# Sensors.net
KiCad netlist of a schematic drawn in Altium Designer
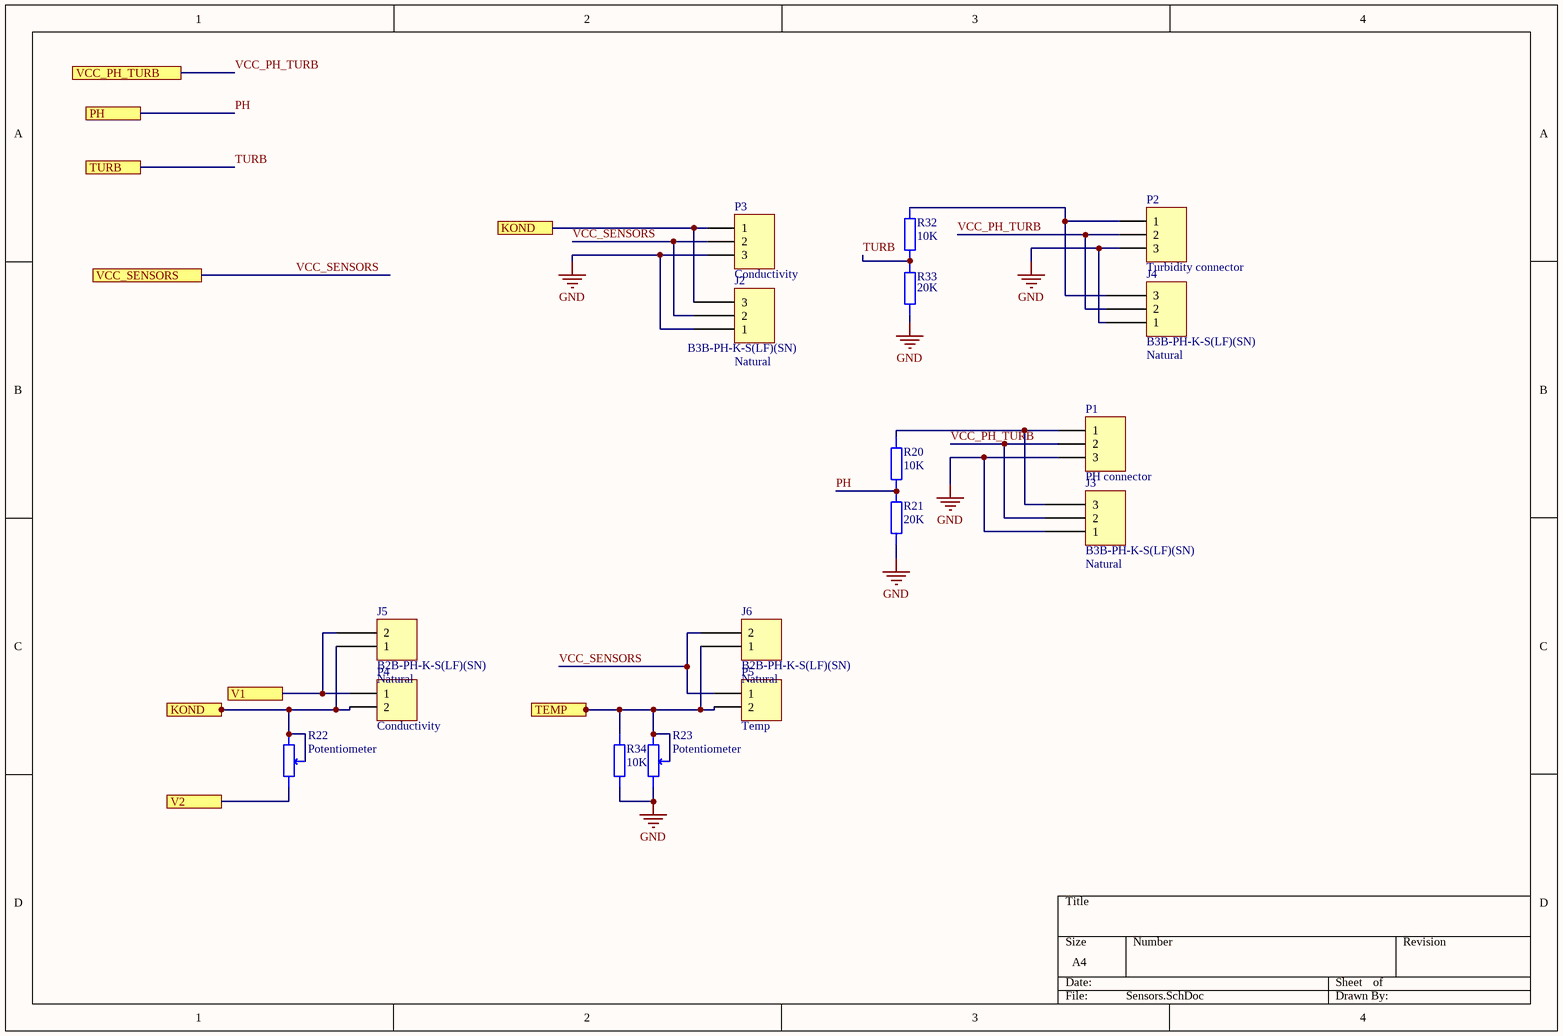
[diagram p0: Sensors.SchDoc]

(export (version "E")
  (design (tool "Eeschema 10.0.6"))
  (components
    (comp (ref "J2")
      (value "B3B-PH-K-S(LF)(SN)")
      (footprint "JST B3B-PH-K")
      (description "CONN HEADER PH TOP 3POS 2MM")
      (fields (field (name "COLOUR") "Natural") (field (name "MANUFACTURER") "JST Sales America Inc."))
      (libsource (lib "Celestial Library Database") (part "3 Pin"))
    )
    (comp (ref "J3")
      (value "B3B-PH-K-S(LF)(SN)")
      (footprint "JST B3B-PH-K")
      (description "CONN HEADER PH TOP 3POS 2MM")
      (fields (field (name "COLOUR") "Natural") (field (name "MANUFACTURER") "JST Sales America Inc."))
      (libsource (lib "Celestial Library Database") (part "3 Pin"))
    )
    (comp (ref "J4")
      (value "B3B-PH-K-S(LF)(SN)")
      (footprint "JST B3B-PH-K")
      (description "CONN HEADER PH TOP 3POS 2MM")
      (fields (field (name "COLOUR") "Natural") (field (name "MANUFACTURER") "JST Sales America Inc."))
      (libsource (lib "Celestial Library Database") (part "3 Pin"))
    )
    (comp (ref "J5")
      (value "B2B-PH-K-S(LF)(SN)")
      (footprint "JST B2B-PH-K")
      (description "CONN HEADER PH TOP 2POS 2MM")
      (fields (field (name "COLOUR") "Natural") (field (name "MANUFACTURER") "JST Sales America Inc."))
      (libsource (lib "Celestial Library Database") (part "2 Pin"))
    )
    (comp (ref "J6")
      (value "B2B-PH-K-S(LF)(SN)")
      (footprint "JST B2B-PH-K")
      (description "CONN HEADER PH TOP 2POS 2MM")
      (fields (field (name "COLOUR") "Natural") (field (name "MANUFACTURER") "JST Sales America Inc."))
      (libsource (lib "Celestial Library Database") (part "2 Pin"))
    )
    (comp (ref "P1")
      (value "PH connector")
      (footprint "HDR1X3")
      (description "Header, 3-Pin")
      (fields (field (name "PUBLISHER") "Altium Limited"))
      (libsource (lib "Miscellaneous Connectors") (part "Header 3"))
    )
    (comp (ref "P2")
      (value "Turbidity connector")
      (footprint "HDR1X3")
      (description "Header, 3-Pin")
      (fields (field (name "PUBLISHER") "Altium Limited"))
      (libsource (lib "Miscellaneous Connectors") (part "Header 3"))
    )
    (comp (ref "P3")
      (value "Conductivity")
      (footprint "HDR1X3")
      (description "Header, 3-Pin")
      (fields (field (name "PUBLISHER") "Altium Limited"))
      (libsource (lib "Miscellaneous Connectors") (part "Header 3"))
    )
    (comp (ref "P4")
      (value "Conductivity")
      (footprint "HDR1X2")
      (description "Header, 2-Pin")
      (fields (field (name "PUBLISHER") "Altium Limited"))
      (libsource (lib "Miscellaneous Connectors") (part "Header 2"))
    )
    (comp (ref "P5")
      (value "Temp")
      (footprint "HDR1X2")
      (description "Header, 2-Pin")
      (fields (field (name "PUBLISHER") "Altium Limited"))
      (libsource (lib "Miscellaneous Connectors") (part "Header 2"))
    )
    (comp (ref "R20")
      (value "10K")
      (footprint "6-0805_L")
      (fields (field (name "TOLERANCE") "1%") (field (name "Comment") "Resistor"))
      (libsource (lib "Schematic Library") (part "Resistor"))
    )
    (comp (ref "R21")
      (value "20K")
      (footprint "6-0805_L")
      (fields (field (name "TOLERANCE") "1%") (field (name "Comment") "Resistor"))
      (libsource (lib "Schematic Library") (part "Resistor"))
    )
    (comp (ref "R22")
      (value "Potentiometer")
      (footprint "Trimmer")
      (libsource (lib "Schematic Library") (part "Potentiometer"))
    )
    (comp (ref "R23")
      (value "Potentiometer")
      (footprint "Trimmer")
      (libsource (lib "Schematic Library") (part "Potentiometer"))
    )
    (comp (ref "R32")
      (value "10K")
      (footprint "6-0805_L")
      (fields (field (name "TOLERANCE") "1%") (field (name "Comment") "Resistor"))
      (libsource (lib "Schematic Library") (part "Resistor"))
    )
    (comp (ref "R33")
      (value "20K")
      (footprint "6-0805_L")
      (fields (field (name "TOLERANCE") "1%") (field (name "Comment") "Resistor"))
      (libsource (lib "Schematic Library") (part "Resistor"))
    )
    (comp (ref "R34")
      (value "10K")
      (footprint "6-0805_L")
      (fields (field (name "TOLERANCE") "1%") (field (name "Comment") "Resistor"))
      (libsource (lib "Schematic Library") (part "Resistor"))
    )
  )
  (nets
    (net (code "1") (name "/KOND") (class "Default")
      (node (ref "J2") (pin "3") (pinfunction "3_3") (pintype "passive"))
      (node (ref "J5") (pin "1") (pinfunction "1_1") (pintype "passive"))
      (node (ref "P3") (pin "1") (pinfunction "1_1") (pintype "passive"))
      (node (ref "P4") (pin "2") (pinfunction "2_2") (pintype "passive"))
      (node (ref "R22") (pin "1") (pinfunction "1_1") (pintype "passive"))
      (node (ref "R22") (pin "3") (pinfunction "3_3") (pintype "passive"))
    )
    (net (code "2") (name "/PH") (class "Default")
      (node (ref "R20") (pin "2") (pinfunction "2_2") (pintype "passive"))
      (node (ref "R21") (pin "1") (pinfunction "1_1") (pintype "passive"))
    )
    (net (code "3") (name "/TEMP") (class "Default")
      (node (ref "J6") (pin "1") (pinfunction "1_1") (pintype "passive"))
      (node (ref "P5") (pin "2") (pinfunction "2_2") (pintype "passive"))
      (node (ref "R23") (pin "1") (pinfunction "1_1") (pintype "passive"))
      (node (ref "R23") (pin "3") (pinfunction "3_3") (pintype "passive"))
      (node (ref "R34") (pin "1") (pinfunction "1_1") (pintype "passive"))
    )
    (net (code "4") (name "/TURB") (class "Default")
      (node (ref "R32") (pin "2") (pinfunction "2_2") (pintype "passive"))
      (node (ref "R33") (pin "1") (pinfunction "1_1") (pintype "passive"))
    )
    (net (code "5") (name "/V1") (class "Default")
      (node (ref "J5") (pin "2") (pinfunction "2_2") (pintype "passive"))
      (node (ref "P4") (pin "1") (pinfunction "1_1") (pintype "passive"))
    )
    (net (code "6") (name "/V2") (class "Default")
      (node (ref "R22") (pin "2") (pinfunction "2_2") (pintype "passive"))
    )
    (net (code "7") (name "/VCC_PH_TURB") (class "Default")
      (node (ref "J3") (pin "2") (pinfunction "2_2") (pintype "passive"))
      (node (ref "J4") (pin "2") (pinfunction "2_2") (pintype "passive"))
      (node (ref "P1") (pin "2") (pinfunction "2_2") (pintype "passive"))
      (node (ref "P2") (pin "2") (pinfunction "2_2") (pintype "passive"))
    )
    (net (code "8") (name "/VCC_SENSORS") (class "Default")
      (node (ref "J2") (pin "2") (pinfunction "2_2") (pintype "passive"))
      (node (ref "J6") (pin "2") (pinfunction "2_2") (pintype "passive"))
      (node (ref "P3") (pin "2") (pinfunction "2_2") (pintype "passive"))
      (node (ref "P5") (pin "1") (pinfunction "1_1") (pintype "passive"))
    )
    (net (code "9") (name "GND") (class "Default")
      (node (ref "J2") (pin "1") (pinfunction "1_1") (pintype "passive"))
      (node (ref "J3") (pin "1") (pinfunction "1_1") (pintype "passive"))
      (node (ref "J4") (pin "1") (pinfunction "1_1") (pintype "passive"))
      (node (ref "P1") (pin "3") (pinfunction "3_3") (pintype "passive"))
      (node (ref "P2") (pin "3") (pinfunction "3_3") (pintype "passive"))
      (node (ref "P3") (pin "3") (pinfunction "3_3") (pintype "passive"))
      (node (ref "R21") (pin "2") (pinfunction "2_2") (pintype "passive"))
      (node (ref "R23") (pin "2") (pinfunction "2_2") (pintype "passive"))
      (node (ref "R33") (pin "2") (pinfunction "2_2") (pintype "passive"))
      (node (ref "R34") (pin "2") (pinfunction "2_2") (pintype "passive"))
    )
    (net (code "10") (name "Net-(J3-Pad3)") (class "Default")
      (node (ref "J3") (pin "3") (pinfunction "3_3") (pintype "passive"))
      (node (ref "P1") (pin "1") (pinfunction "1_1") (pintype "passive"))
      (node (ref "R20") (pin "1") (pinfunction "1_1") (pintype "passive"))
    )
    (net (code "11") (name "Net-(J4-Pad3)") (class "Default")
      (node (ref "J4") (pin "3") (pinfunction "3_3") (pintype "passive"))
      (node (ref "P2") (pin "1") (pinfunction "1_1") (pintype "passive"))
      (node (ref "R32") (pin "1") (pinfunction "1_1") (pintype "passive"))
    )
  )
)
